# 469135_003_3.net
KiCad netlist of a schematic drawn in Altium Designer
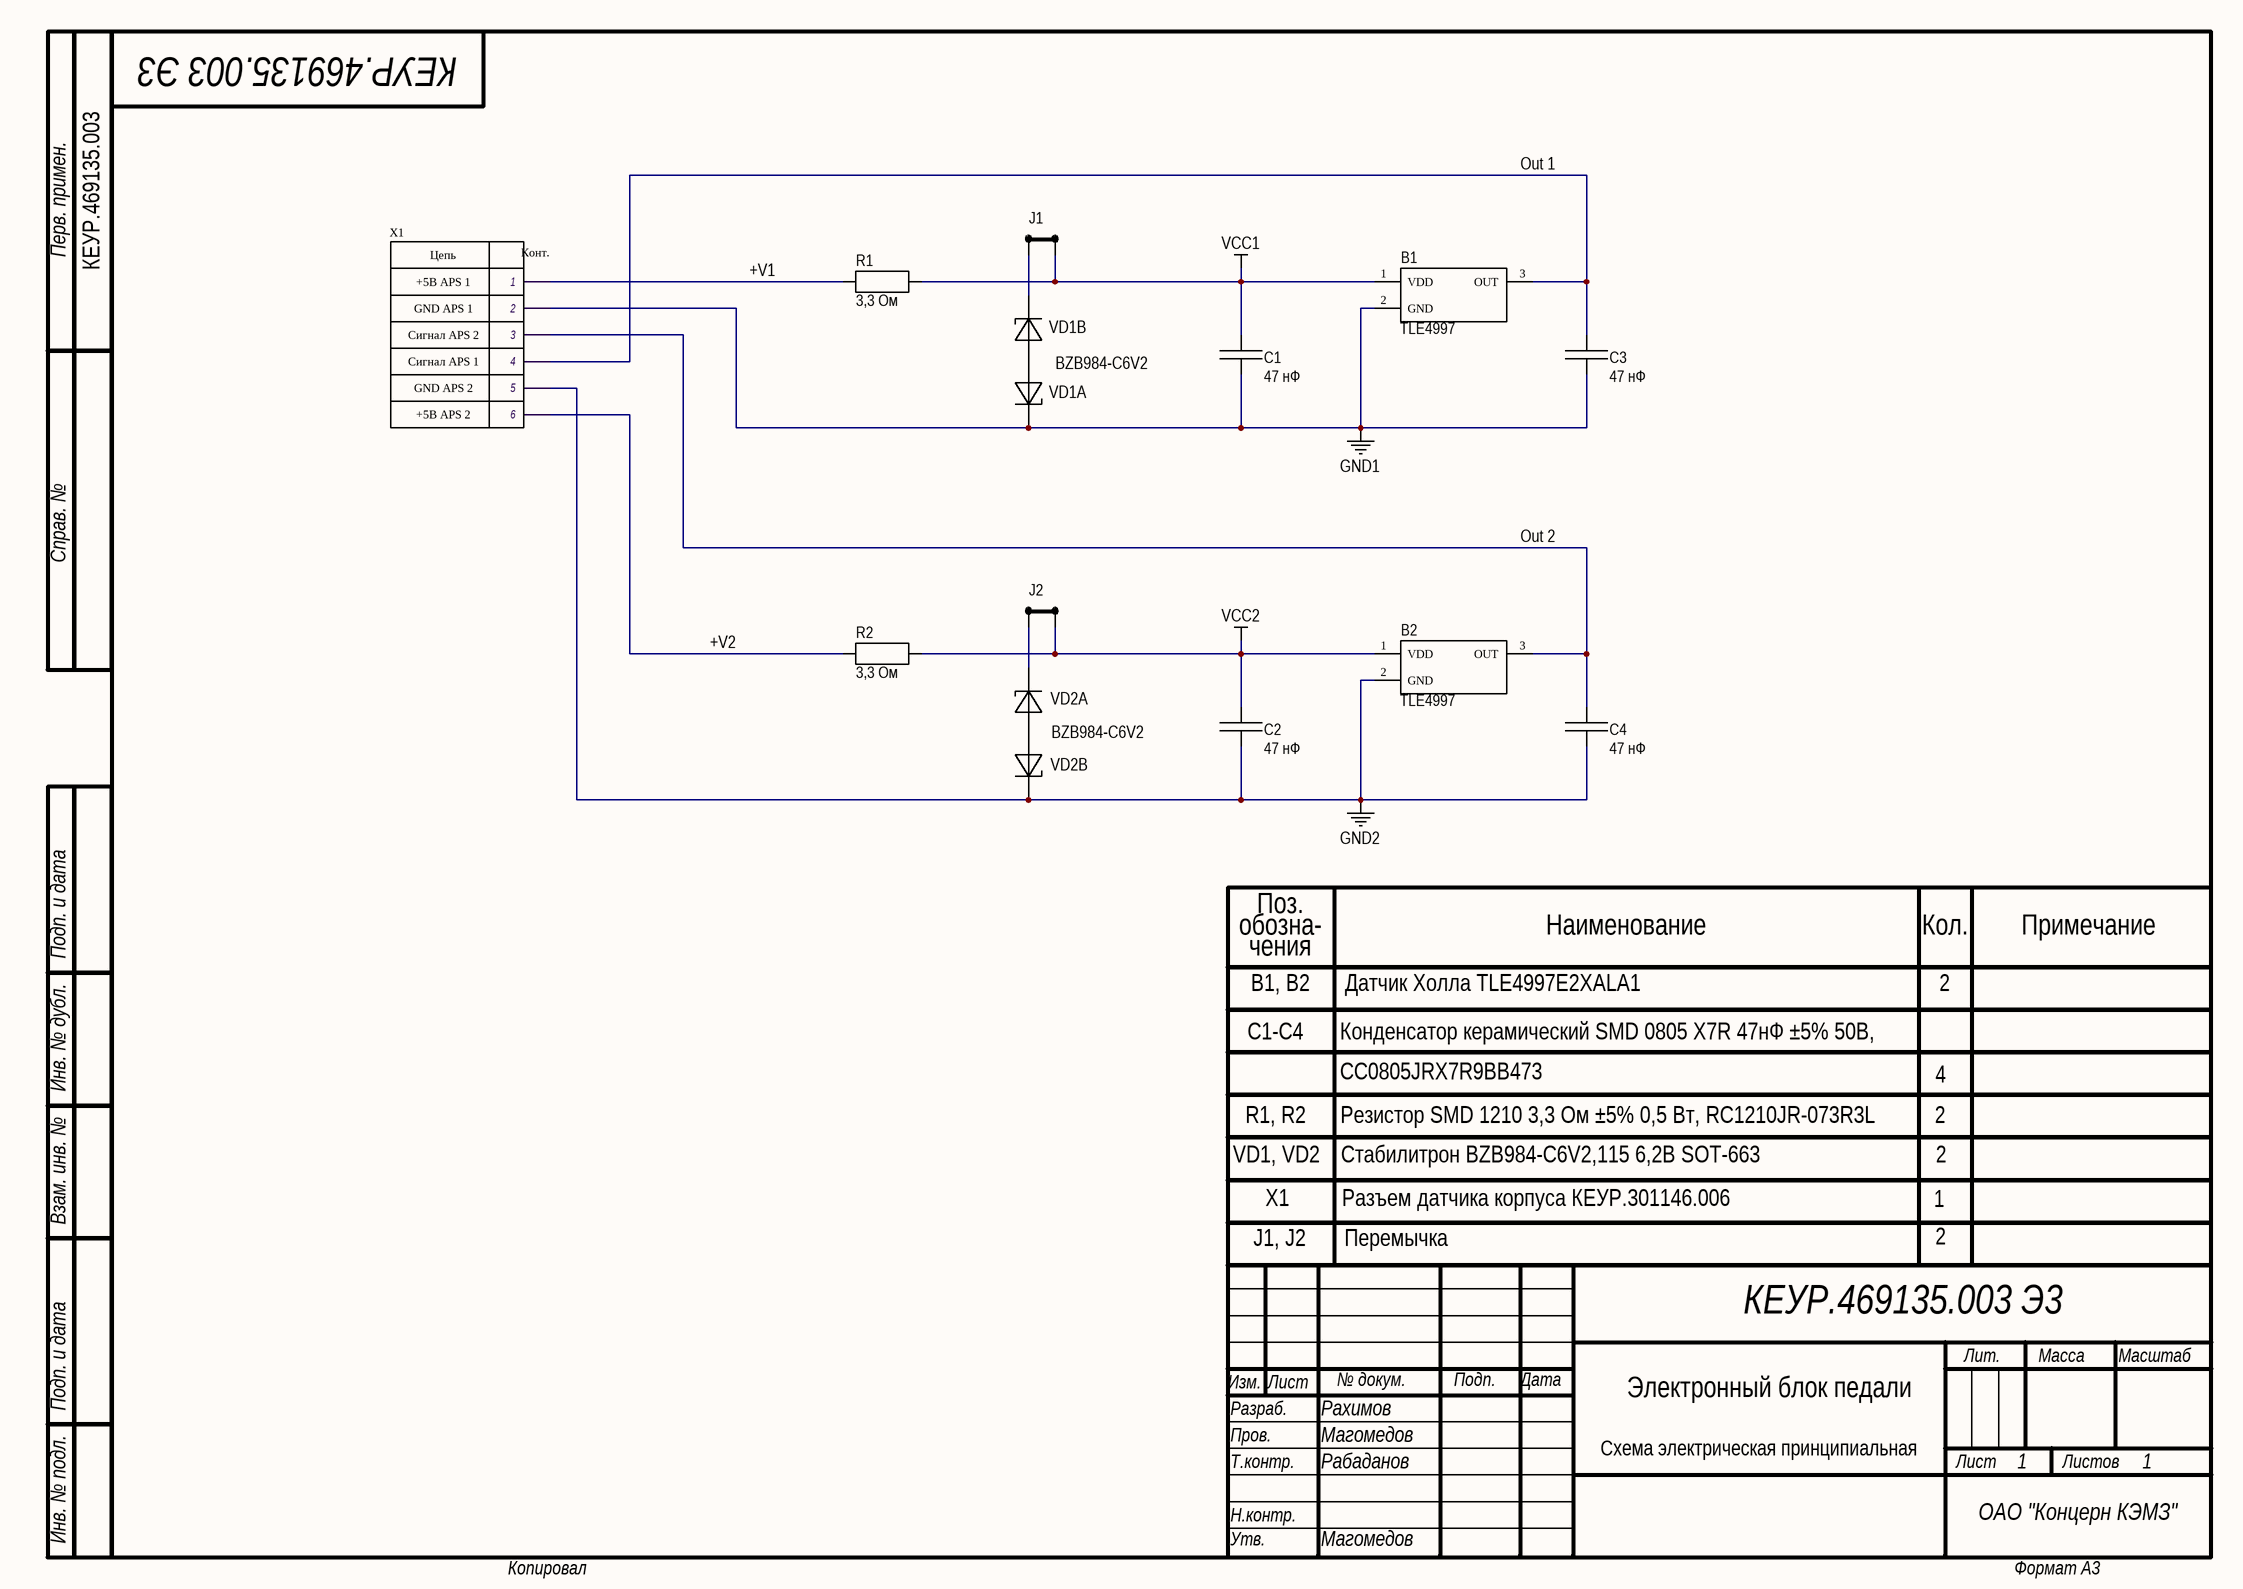
[diagram p0: Электронный блок педали. Схема принципиальная. КЕУР.469135.003Э3.SchDoc]

(export (version "E")
  (design (tool "Eeschema 10.0.6"))
  (components
    (comp (ref "B1")
      (value "TLE4997")
      (footprint "PG-SSO-3-10")
      (description "Hall Effect Sensor Single Axis PG-SSO-3-92")
      (libsource (lib "Sensors") (part "TLE4997"))
    )
    (comp (ref "B2")
      (value "TLE4997")
      (footprint "PG-SSO-3-10")
      (description "Hall Effect Sensor Single Axis PG-SSO-3-92")
      (libsource (lib "Sensors") (part "TLE4997"))
    )
    (comp (ref "C1")
      (value "47 нФ")
      (footprint "C0805")
      (description "0.047 µF ±5% 50V Ceramic Capacitor X7R 0805 (2012 Metric)")
      (fields (field (name "TOLERANCE") "±5%") (field (name "VOLTAGE") "50 В"))
      (libsource (lib "Capacitors") (part "Capacity"))
    )
    (comp (ref "C2")
      (value "47 нФ")
      (footprint "C0805")
      (description "0.047 µF ±5% 50V Ceramic Capacitor X7R 0805 (2012 Metric)")
      (fields (field (name "TOLERANCE") "±5%") (field (name "VOLTAGE") "50 В"))
      (libsource (lib "Capacitors") (part "Capacity"))
    )
    (comp (ref "C3")
      (value "47 нФ")
      (footprint "C0805")
      (description "0.047 µF ±5% 50V Ceramic Capacitor X7R 0805 (2012 Metric)")
      (fields (field (name "TOLERANCE") "±5%") (field (name "VOLTAGE") "50 В"))
      (libsource (lib "Capacitors") (part "Capacity"))
    )
    (comp (ref "C4")
      (value "47 нФ")
      (footprint "C0805")
      (description "0.047 µF ±5% 50V Ceramic Capacitor X7R 0805 (2012 Metric)")
      (fields (field (name "TOLERANCE") "±5%") (field (name "VOLTAGE") "50 В"))
      (libsource (lib "Capacitors") (part "Capacity"))
    )
    (comp (ref "J1") (value "~") (footprint "J-2x2-2.5") (libsource (lib "Jamper") (part "Jamper")))
    (comp (ref "J2") (value "~") (footprint "J-2x2-2.5") (libsource (lib "Jamper") (part "Jamper")))
    (comp (ref "R1")
      (value "3,3 Ом")
      (footprint "R1210")
      (description "20 Ohms ±5% 0.5W, 1/2W Chip Resistor 1210 (3225 Metric) Moisture Resistant Thick Film")
      (fields (field (name "POWER") "0,5Вт") (field (name "TOLERANCE") "±5%"))
      (libsource (lib "Resistors") (part "Resistor"))
    )
    (comp (ref "R2")
      (value "3,3 Ом")
      (footprint "R1210")
      (description "20 Ohms ±5% 0.5W, 1/2W Chip Resistor 1210 (3225 Metric) Moisture Resistant Thick Film")
      (fields (field (name "POWER") "0,5Вт") (field (name "TOLERANCE") "±5%"))
      (libsource (lib "Resistors") (part "Resistor"))
    )
    (comp (ref "VD1")
      (value "BZB984-C6V2")
      (footprint "SOT-663")
      (description "Zener Diode Array 1 Pair Common Anode 6.2 V 265 mW ±5% SOT-663")
      (libsource (lib "Diode") (part "BZB984-C6V2,115"))
    )
    (comp (ref "VD2")
      (value "BZB984-C6V2")
      (footprint "SOT-663")
      (description "Zener Diode Array 1 Pair Common Anode 6.2 V 265 mW ±5% SOT-663")
      (libsource (lib "Diode") (part "BZB984-C6V2,115"))
    )
    (comp (ref "X1")
      (value "~")
      (footprint "Датчик ПАЭ-2")
      (fields
        (field (name "КОНТ.1") "+5В APS 1")
        (field (name "КОНТ.2") "GND APS 1")
        (field (name "КОНТ.3") "Сигнал APS 2")
        (field (name "КОНТ.4") "Сигнал APS 1")
        (field (name "КОНТ.5") "GND APS 2")
        (field (name "КОНТ.6") "+5В APS 2")
      )
      (libsource (lib "Connectors") (part "Разъем на плате-06"))
    )
  )
  (nets
    (net (code "1") (name "/+V1") (class "Default")
      (node (ref "R1") (pin "1") (pintype "passive"))
      (node (ref "X1") (pin "1") (pinfunction "1_1") (pintype "passive"))
    )
    (net (code "2") (name "/+V2") (class "Default")
      (node (ref "R2") (pin "1") (pintype "passive"))
      (node (ref "X1") (pin "6") (pinfunction "6_6") (pintype "passive"))
    )
    (net (code "3") (name "/Out 1") (class "Default")
      (node (ref "B1") (pin "3") (pinfunction "OUT_3") (pintype "passive"))
      (node (ref "C3") (pin "2") (pinfunction "2_2") (pintype "passive"))
      (node (ref "X1") (pin "4") (pinfunction "4_4") (pintype "passive"))
    )
    (net (code "4") (name "/Out 2") (class "Default")
      (node (ref "B2") (pin "3") (pinfunction "OUT_3") (pintype "passive"))
      (node (ref "C4") (pin "2") (pinfunction "2_2") (pintype "passive"))
      (node (ref "X1") (pin "3") (pinfunction "3_3") (pintype "passive"))
    )
    (net (code "5") (name "GND1") (class "Default")
      (node (ref "B1") (pin "2") (pinfunction "GND_2") (pintype "passive"))
      (node (ref "C1") (pin "1") (pinfunction "1_1") (pintype "passive"))
      (node (ref "C3") (pin "1") (pinfunction "1_1") (pintype "passive"))
      (node (ref "VD1") (pin "1") (pinfunction "C_1") (pintype "passive"))
      (node (ref "X1") (pin "2") (pinfunction "2_2") (pintype "passive"))
    )
    (net (code "6") (name "GND2") (class "Default")
      (node (ref "B2") (pin "2") (pinfunction "GND_2") (pintype "passive"))
      (node (ref "C2") (pin "1") (pinfunction "1_1") (pintype "passive"))
      (node (ref "C4") (pin "1") (pinfunction "1_1") (pintype "passive"))
      (node (ref "VD2") (pin "2") (pinfunction "C_2") (pintype "passive"))
      (node (ref "X1") (pin "5") (pinfunction "5_5") (pintype "passive"))
    )
    (net (code "7") (name "Net-(VD1A-A)") (class "Default")
      (node (ref "VD1") (pin "3") (pinfunction "A_3") (pintype "passive"))
    )
    (net (code "8") (name "Net-(VD1B-C)") (class "Default")
      (node (ref "J1") (pin "1") (pintype "passive"))
      (node (ref "VD1") (pin "2") (pinfunction "C_2") (pintype "passive"))
    )
    (net (code "9") (name "Net-(VD2A-A)") (class "Default")
      (node (ref "VD2") (pin "3") (pinfunction "A_3") (pintype "passive"))
    )
    (net (code "10") (name "Net-(VD2A-C)") (class "Default")
      (node (ref "J2") (pin "1") (pintype "passive"))
      (node (ref "VD2") (pin "1") (pinfunction "C_1") (pintype "passive"))
    )
    (net (code "11") (name "VCC1") (class "Default")
      (node (ref "B1") (pin "1") (pinfunction "VDD_1") (pintype "passive"))
      (node (ref "C1") (pin "2") (pinfunction "2_2") (pintype "passive"))
      (node (ref "J1") (pin "2") (pintype "passive"))
      (node (ref "R1") (pin "2") (pintype "passive"))
    )
    (net (code "12") (name "VCC2") (class "Default")
      (node (ref "B2") (pin "1") (pinfunction "VDD_1") (pintype "passive"))
      (node (ref "C2") (pin "2") (pinfunction "2_2") (pintype "passive"))
      (node (ref "J2") (pin "2") (pintype "passive"))
      (node (ref "R2") (pin "2") (pintype "passive"))
    )
  )
)
